# TT1-1-Top.net
KiCad netlist of a schematic drawn in Altium Designer
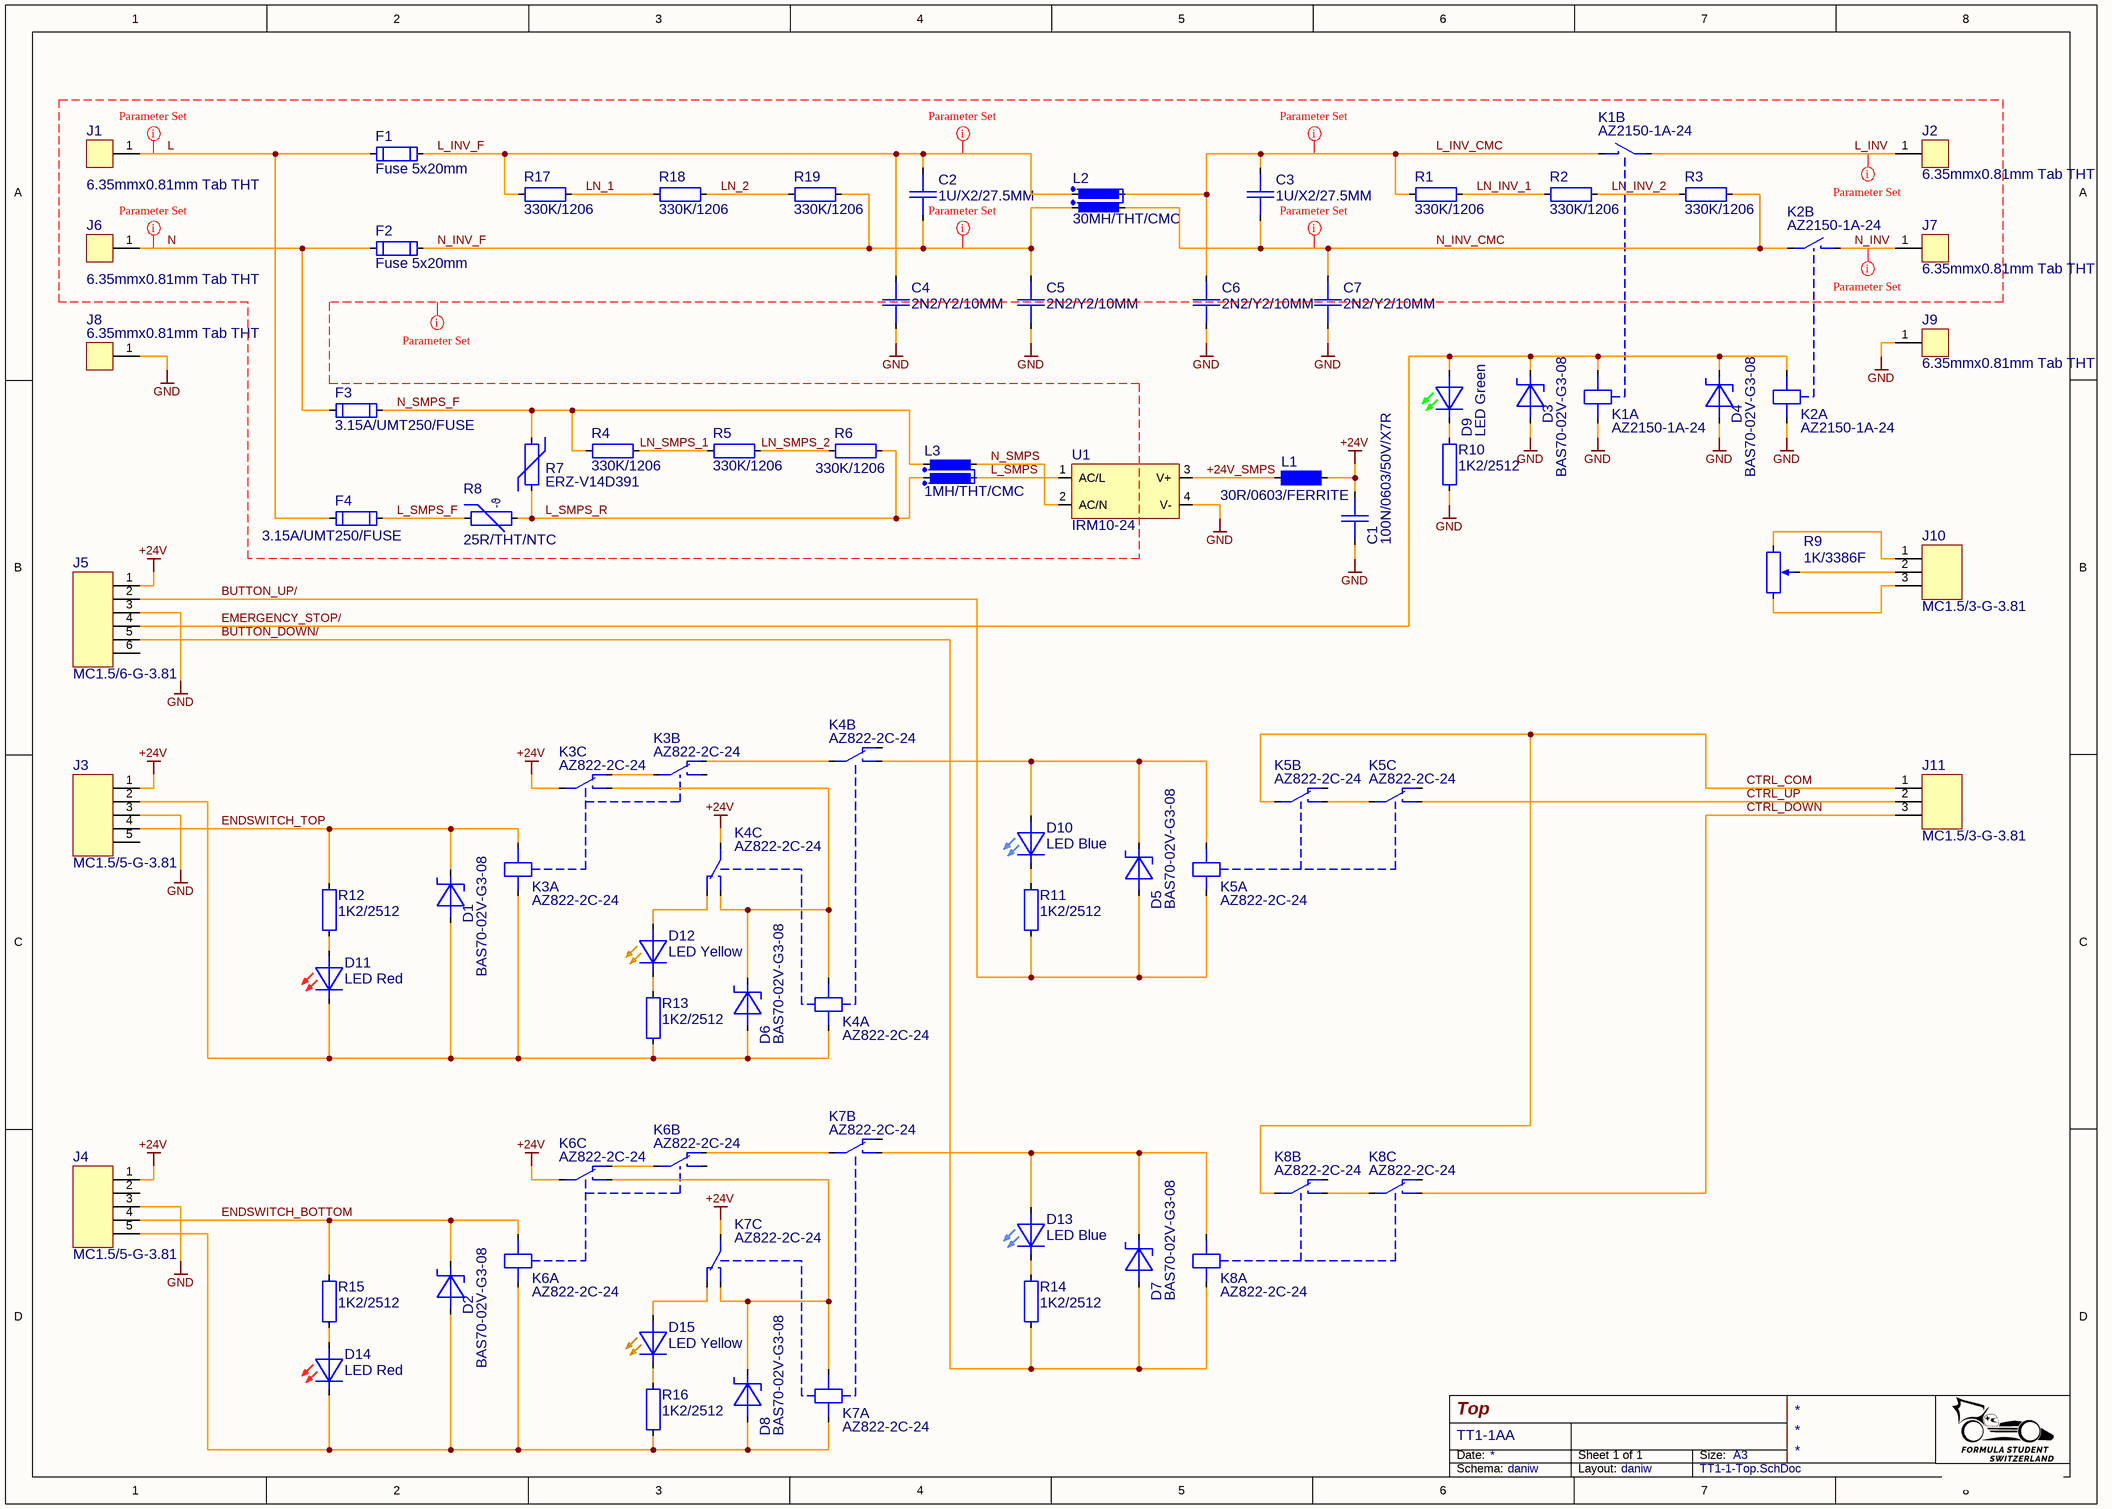
[diagram p0: TT1-1-Top.SchDoc]

(export (version "E")
  (design (tool "Eeschema 10.0.6"))
  (components
    (comp (ref "C1")
      (value "100N/0603/50V/X7R")
      (footprint "CAP0603_X7R")
      (description "CAP SM 0603 100nF 50V X7R")
      (fields (field (name "MANUFACTURER") "GENERIC"))
      (libsource (lib "daniw_altium_lib") (part "C"))
    )
    (comp (ref "C2")
      (value "1U/X2/27.5MM")
      (footprint "CAP2750P315X110X190-BL")
      (description "CAP THT 31.5X11X19 1uF 305V X2")
      (fields (field (name "MANUFACTURER") "GENERIC"))
      (libsource (lib "daniw_altium_lib") (part "C"))
    )
    (comp (ref "C3")
      (value "1U/X2/27.5MM")
      (footprint "CAP2750P315X110X190-BL")
      (description "CAP THT 31.5X11X19 1uF 305V X2")
      (fields (field (name "MANUFACTURER") "GENERIC"))
      (libsource (lib "daniw_altium_lib") (part "C"))
    )
    (comp (ref "C4")
      (value "2N2/Y2/10MM")
      (footprint "CAP1000P130X40X90-BL")
      (description "CAP THT 13X4X9 2.2nF 300V Y2")
      (fields (field (name "MANUFACTURER") "GENERIC"))
      (libsource (lib "daniw_altium_lib") (part "C"))
    )
    (comp (ref "C5")
      (value "2N2/Y2/10MM")
      (footprint "CAP1000P130X40X90-BL")
      (description "CAP THT 13X4X9 2.2nF 300V Y2")
      (fields (field (name "MANUFACTURER") "GENERIC"))
      (libsource (lib "daniw_altium_lib") (part "C"))
    )
    (comp (ref "C6")
      (value "2N2/Y2/10MM")
      (footprint "CAP1000P130X40X90-BL")
      (description "CAP THT 13X4X9 2.2nF 300V Y2")
      (fields (field (name "MANUFACTURER") "GENERIC"))
      (libsource (lib "daniw_altium_lib") (part "C"))
    )
    (comp (ref "C7")
      (value "2N2/Y2/10MM")
      (footprint "CAP1000P130X40X90-BL")
      (description "CAP THT 13X4X9 2.2nF 300V Y2")
      (fields (field (name "MANUFACTURER") "GENERIC"))
      (libsource (lib "daniw_altium_lib") (part "C"))
    )
    (comp (ref "D1")
      (value "BAS70-02V-G3-08")
      (footprint "SOD1608X065")
      (description "Small Signal Schottky Diode")
      (fields (field (name "MANUFACTURER") "Vishay"))
      (libsource (lib "daniw_altium_lib") (part "D_Schottky"))
    )
    (comp (ref "D2")
      (value "BAS70-02V-G3-08")
      (footprint "SOD1608X065")
      (description "Small Signal Schottky Diode")
      (fields (field (name "MANUFACTURER") "Vishay"))
      (libsource (lib "daniw_altium_lib") (part "D_Schottky"))
    )
    (comp (ref "D3")
      (value "BAS70-02V-G3-08")
      (footprint "SOD1608X065")
      (description "Small Signal Schottky Diode")
      (fields (field (name "MANUFACTURER") "Vishay"))
      (libsource (lib "daniw_altium_lib") (part "D_Schottky"))
    )
    (comp (ref "D4")
      (value "BAS70-02V-G3-08")
      (footprint "SOD1608X065")
      (description "Small Signal Schottky Diode")
      (fields (field (name "MANUFACTURER") "Vishay"))
      (libsource (lib "daniw_altium_lib") (part "D_Schottky"))
    )
    (comp (ref "D5")
      (value "BAS70-02V-G3-08")
      (footprint "SOD1608X065")
      (description "Small Signal Schottky Diode")
      (fields (field (name "MANUFACTURER") "Vishay"))
      (libsource (lib "daniw_altium_lib") (part "D_Schottky"))
    )
    (comp (ref "D6")
      (value "BAS70-02V-G3-08")
      (footprint "SOD1608X065")
      (description "Small Signal Schottky Diode")
      (fields (field (name "MANUFACTURER") "Vishay"))
      (libsource (lib "daniw_altium_lib") (part "D_Schottky"))
    )
    (comp (ref "D7")
      (value "BAS70-02V-G3-08")
      (footprint "SOD1608X065")
      (description "Small Signal Schottky Diode")
      (fields (field (name "MANUFACTURER") "Vishay"))
      (libsource (lib "daniw_altium_lib") (part "D_Schottky"))
    )
    (comp (ref "D8")
      (value "BAS70-02V-G3-08")
      (footprint "SOD1608X065")
      (description "Small Signal Schottky Diode")
      (fields (field (name "MANUFACTURER") "Vishay"))
      (libsource (lib "daniw_altium_lib") (part "D_Schottky"))
    )
    (comp (ref "D9")
      (value "LED Green")
      (footprint "LED0603_GREEN")
      (description "Generic LED Green 0603")
      (fields (field (name "PART NUMBER") "LED Green 0603") (field (name "MANUFACTURER") "GENERIC"))
      (libsource (lib "daniw_altium_lib") (part "LED_GREEN"))
    )
    (comp (ref "D10")
      (value "LED Blue")
      (footprint "LED0603_BLUE")
      (description "Generic LED Blue 0603")
      (fields (field (name "PART NUMBER") "LED Blue 0603") (field (name "MANUFACTURER") "GENERIC"))
      (libsource (lib "daniw_altium_lib") (part "LED_BLUE"))
    )
    (comp (ref "D11")
      (value "LED Red")
      (footprint "LED0603_RED")
      (description "Generic LED Red 0603")
      (fields (field (name "PART NUMBER") "LED Red 0603") (field (name "MANUFACTURER") "GENERIC"))
      (libsource (lib "daniw_altium_lib") (part "LED_RED"))
    )
    (comp (ref "D12")
      (value "LED Yellow")
      (footprint "LED0603_YELLOW")
      (description "Generic LED Yellow 0603")
      (fields (field (name "PART NUMBER") "LED Yellow 0603") (field (name "MANUFACTURER") "GENERIC"))
      (libsource (lib "daniw_altium_lib") (part "LED_YELLOW"))
    )
    (comp (ref "D13")
      (value "LED Blue")
      (footprint "LED0603_BLUE")
      (description "Generic LED Blue 0603")
      (fields (field (name "PART NUMBER") "LED Blue 0603") (field (name "MANUFACTURER") "GENERIC"))
      (libsource (lib "daniw_altium_lib") (part "LED_BLUE"))
    )
    (comp (ref "D14")
      (value "LED Red")
      (footprint "LED0603_RED")
      (description "Generic LED Red 0603")
      (fields (field (name "PART NUMBER") "LED Red 0603") (field (name "MANUFACTURER") "GENERIC"))
      (libsource (lib "daniw_altium_lib") (part "LED_RED"))
    )
    (comp (ref "D15")
      (value "LED Yellow")
      (footprint "LED0603_YELLOW")
      (description "Generic LED Yellow 0603")
      (fields (field (name "PART NUMBER") "LED Yellow 0603") (field (name "MANUFACTURER") "GENERIC"))
      (libsource (lib "daniw_altium_lib") (part "LED_YELLOW"))
    )
    (comp (ref "F1")
      (value "Fuse 5x20mm")
      (footprint "OGN_THR")
      (description "open fuse holder, 5 x 20 mm, THR, IEC 60335-1")
      (fields (field (name "PART NUMBER") "Fuse/5x20mm/OGN") (field (name "MANUFACTURER") "Schurter"))
      (libsource (lib "daniw_altium_lib") (part "Fuse"))
    )
    (comp (ref "F2")
      (value "Fuse 5x20mm")
      (footprint "OGN_THR")
      (description "open fuse holder, 5 x 20 mm, THR, IEC 60335-1")
      (fields (field (name "PART NUMBER") "Fuse/5x20mm/OGN") (field (name "MANUFACTURER") "Schurter"))
      (libsource (lib "daniw_altium_lib") (part "Fuse"))
    )
    (comp (ref "F3")
      (value "3.15A/UMT250/FUSE")
      (footprint "UMT250")
      (description "Fuse 250VAC 3.15A UMT250")
      (fields (field (name "MANUFACTURER") "Schurter"))
      (libsource (lib "daniw_altium_lib") (part "Fuse"))
    )
    (comp (ref "F4")
      (value "3.15A/UMT250/FUSE")
      (footprint "UMT250")
      (description "Fuse 250VAC 3.15A UMT250")
      (fields (field (name "MANUFACTURER") "Schurter"))
      (libsource (lib "daniw_altium_lib") (part "Fuse"))
    )
    (comp (ref "J1")
      (value "6.35mmx0.81mm Tab THT")
      (footprint "Tab_THT_635")
      (description "CONN QC TAB 0.250 SOLDER")
      (fields (field (name "PART NUMBER") "Tab_025_THT") (field (name "MANUFACTURER") "GENERIC"))
      (libsource (lib "daniw_altium_lib") (part "CON1"))
    )
    (comp (ref "J2")
      (value "6.35mmx0.81mm Tab THT")
      (footprint "Tab_THT_635")
      (description "CONN QC TAB 0.250 SOLDER")
      (fields (field (name "PART NUMBER") "Tab_025_THT") (field (name "MANUFACTURER") "GENERIC"))
      (libsource (lib "") (part "CON1_1"))
    )
    (comp (ref "J3")
      (value "MC1.5/5-G-3.81")
      (footprint "MC1.5/5-G-3.81")
      (description "Phoenix contact MC 1,5/ 5-G-3,81")
      (fields (field (name "MANUFACTURER") "Phoenix"))
      (libsource (lib "daniw_altium_lib") (part "CON5"))
    )
    (comp (ref "J4")
      (value "MC1.5/5-G-3.81")
      (footprint "MC1.5/5-G-3.81")
      (description "Phoenix contact MC 1,5/ 5-G-3,81")
      (fields (field (name "MANUFACTURER") "Phoenix"))
      (libsource (lib "daniw_altium_lib") (part "CON5"))
    )
    (comp (ref "J5")
      (value "MC1.5/6-G-3.81")
      (footprint "MC1.5/6-G-3.81")
      (description "Phoenix contact MC 1,5/ 6-G-3,81")
      (fields (field (name "MANUFACTURER") "Phoenix"))
      (libsource (lib "daniw_altium_lib") (part "CON6"))
    )
    (comp (ref "J6")
      (value "6.35mmx0.81mm Tab THT")
      (footprint "Tab_THT_635")
      (description "CONN QC TAB 0.250 SOLDER")
      (fields (field (name "PART NUMBER") "Tab_025_THT") (field (name "MANUFACTURER") "GENERIC"))
      (libsource (lib "daniw_altium_lib") (part "CON1"))
    )
    (comp (ref "J7")
      (value "6.35mmx0.81mm Tab THT")
      (footprint "Tab_THT_635")
      (description "CONN QC TAB 0.250 SOLDER")
      (fields (field (name "PART NUMBER") "Tab_025_THT") (field (name "MANUFACTURER") "GENERIC"))
      (libsource (lib "") (part "CON1_1"))
    )
    (comp (ref "J8")
      (value "6.35mmx0.81mm Tab THT")
      (footprint "Tab_THT_635")
      (description "CONN QC TAB 0.250 SOLDER")
      (fields (field (name "PART NUMBER") "Tab_025_THT") (field (name "MANUFACTURER") "GENERIC"))
      (libsource (lib "daniw_altium_lib") (part "CON1"))
    )
    (comp (ref "J9")
      (value "6.35mmx0.81mm Tab THT")
      (footprint "Tab_THT_635")
      (description "CONN QC TAB 0.250 SOLDER")
      (fields (field (name "PART NUMBER") "Tab_025_THT") (field (name "MANUFACTURER") "GENERIC"))
      (libsource (lib "") (part "CON1_1"))
    )
    (comp (ref "J10")
      (value "MC1.5/3-G-3.81")
      (footprint "MC1.5/3-G-3.81")
      (description "Phoenix contact MC 1,5/ 3-G-3,81")
      (fields (field (name "MANUFACTURER") "Phoenix"))
      (libsource (lib "daniw_altium_lib") (part "CON3"))
    )
    (comp (ref "J11")
      (value "MC1.5/3-G-3.81")
      (footprint "MC1.5/3-G-3.81")
      (description "Phoenix contact MC 1,5/ 3-G-3,81")
      (fields (field (name "MANUFACTURER") "Phoenix"))
      (libsource (lib "daniw_altium_lib") (part "CON3"))
    )
    (comp (ref "K1")
      (value "AZ2150-1A-24")
      (footprint "AZ2150-SPST-NO")
      (description "Miniature Power Relay, SPST-NO, 24V Coil, 40A 30VDC 300VAC")
      (fields (field (name "MANUFACTURER") "Zettler"))
      (libsource (lib "daniw_altium_lib") (part "REL_SPST_NO"))
    )
    (comp (ref "K2")
      (value "AZ2150-1A-24")
      (footprint "AZ2150-SPST-NO")
      (description "Miniature Power Relay, SPST-NO, 24V Coil, 40A 30VDC 300VAC")
      (fields (field (name "MANUFACTURER") "Zettler"))
      (libsource (lib "daniw_altium_lib") (part "REL_SPST_NO"))
    )
    (comp (ref "K3")
      (value "AZ822-2C-24")
      (footprint "AZ822")
      (description "Subminiature DIP Relay, DPDT, 24V 98mW Coil, 2A 220VDC 250VAC")
      (fields (field (name "MANUFACTURER") "Zettler"))
      (libsource (lib "daniw_altium_lib") (part "REL_DPDT"))
    )
    (comp (ref "K4")
      (value "AZ822-2C-24")
      (footprint "AZ822")
      (description "Subminiature DIP Relay, DPDT, 24V 98mW Coil, 2A 220VDC 250VAC")
      (fields (field (name "MANUFACTURER") "Zettler"))
      (libsource (lib "daniw_altium_lib") (part "REL_DPDT"))
    )
    (comp (ref "K5")
      (value "AZ822-2C-24")
      (footprint "AZ822")
      (description "Subminiature DIP Relay, DPDT, 24V 98mW Coil, 2A 220VDC 250VAC")
      (fields (field (name "MANUFACTURER") "Zettler"))
      (libsource (lib "daniw_altium_lib") (part "REL_DPDT"))
    )
    (comp (ref "K6")
      (value "AZ822-2C-24")
      (footprint "AZ822")
      (description "Subminiature DIP Relay, DPDT, 24V 98mW Coil, 2A 220VDC 250VAC")
      (fields (field (name "MANUFACTURER") "Zettler"))
      (libsource (lib "daniw_altium_lib") (part "REL_DPDT"))
    )
    (comp (ref "K7")
      (value "AZ822-2C-24")
      (footprint "AZ822")
      (description "Subminiature DIP Relay, DPDT, 24V 98mW Coil, 2A 220VDC 250VAC")
      (fields (field (name "MANUFACTURER") "Zettler"))
      (libsource (lib "daniw_altium_lib") (part "REL_DPDT"))
    )
    (comp (ref "K8")
      (value "AZ822-2C-24")
      (footprint "AZ822")
      (description "Subminiature DIP Relay, DPDT, 24V 98mW Coil, 2A 220VDC 250VAC")
      (fields (field (name "MANUFACTURER") "Zettler"))
      (libsource (lib "daniw_altium_lib") (part "REL_DPDT"))
    )
    (comp (ref "L1")
      (value "30R/0603/FERRITE")
      (footprint "FB0603")
      (description "30R@100MHz 5A 0603 Ferrite")
      (fields (field (name "MANUFACTURER") "GENERIC"))
      (libsource (lib "daniw_altium_lib") (part "Ferrite"))
    )
    (comp (ref "L2")
      (value "30MH/THT/CMC")
      (footprint "CMC-WE-CMBNC-XL-7448050530")
      (description "CMC 30mH 5A Würth CMBNC 7448050530")
      (fields (field (name "MANUFACTURER") "Würth"))
      (libsource (lib "daniw_altium_lib") (part "L_CMC_2"))
    )
    (comp (ref "L3")
      (value "1MH/THT/CMC")
      (footprint "DFKH-CASE-50-2")
      (description "CMC 1mH 2A THT Schurter DFKH-14-0003")
      (fields (field (name "MANUFACTURER") "SCHURTER"))
      (libsource (lib "") (part "L_CMC_2_1"))
    )
    (comp (ref "R1")
      (value "330K/1206")
      (footprint "R1206-0.80-WW")
      (description "RES SM 1206 330K")
      (fields (field (name "MANUFACTURER") "GENERIC"))
      (libsource (lib "daniw_altium_lib") (part "R"))
    )
    (comp (ref "R2")
      (value "330K/1206")
      (footprint "R1206-0.80-WW")
      (description "RES SM 1206 330K")
      (fields (field (name "MANUFACTURER") "GENERIC"))
      (libsource (lib "daniw_altium_lib") (part "R"))
    )
    (comp (ref "R3")
      (value "330K/1206")
      (footprint "R1206-0.80-WW")
      (description "RES SM 1206 330K")
      (fields (field (name "MANUFACTURER") "GENERIC"))
      (libsource (lib "daniw_altium_lib") (part "R"))
    )
    (comp (ref "R4")
      (value "330K/1206")
      (footprint "R1206-0.80-WW")
      (description "RES SM 1206 330K")
      (fields (field (name "MANUFACTURER") "GENERIC"))
      (libsource (lib "daniw_altium_lib") (part "R"))
    )
    (comp (ref "R5")
      (value "330K/1206")
      (footprint "R1206-0.80-WW")
      (description "RES SM 1206 330K")
      (fields (field (name "MANUFACTURER") "GENERIC"))
      (libsource (lib "daniw_altium_lib") (part "R"))
    )
    (comp (ref "R6")
      (value "330K/1206")
      (footprint "R1206-0.80-WW")
      (description "RES SM 1206 330K")
      (fields (field (name "MANUFACTURER") "GENERIC"))
      (libsource (lib "daniw_altium_lib") (part "R"))
    )
    (comp (ref "R7")
      (value "ERZ-V14D391")
      (footprint "RESD750W80D155")
      (description "VARISTOR 391V 6kA")
      (fields (field (name "MANUFACTURER") "GENERIC"))
      (libsource (lib "daniw_altium_lib") (part "R_VAR"))
    )
    (comp (ref "R8")
      (value "25R/THT/NTC")
      (footprint "RESD500W60D115")
      (description "RES NTC THT 5 25R")
      (fields (field (name "MANUFACTURER") "GENERIC"))
      (libsource (lib "daniw_altium_lib") (part "R_NTC"))
    )
    (comp (ref "R9")
      (value "1K/3386F")
      (footprint "3386F")
      (description "RES POT 3386F 1K")
      (fields (field (name "MANUFACTURER") "Bourns"))
      (libsource (lib "daniw_altium_lib") (part "R_POT"))
    )
    (comp (ref "R10")
      (value "1K2/2512")
      (footprint "R2512-0.65-WW")
      (description "RES SM 2512 1K2")
      (fields (field (name "MANUFACTURER") "GENERIC"))
      (libsource (lib "daniw_altium_lib") (part "R"))
    )
    (comp (ref "R11")
      (value "1K2/2512")
      (footprint "R2512-0.65-WW")
      (description "RES SM 2512 1K2")
      (fields (field (name "MANUFACTURER") "GENERIC"))
      (libsource (lib "daniw_altium_lib") (part "R"))
    )
    (comp (ref "R12")
      (value "1K2/2512")
      (footprint "R2512-0.65-WW")
      (description "RES SM 2512 1K2")
      (fields (field (name "MANUFACTURER") "GENERIC"))
      (libsource (lib "daniw_altium_lib") (part "R"))
    )
    (comp (ref "R13")
      (value "1K2/2512")
      (footprint "R2512-0.65-WW")
      (description "RES SM 2512 1K2")
      (fields (field (name "MANUFACTURER") "GENERIC"))
      (libsource (lib "daniw_altium_lib") (part "R"))
    )
    (comp (ref "R14")
      (value "1K2/2512")
      (footprint "R2512-0.65-WW")
      (description "RES SM 2512 1K2")
      (fields (field (name "MANUFACTURER") "GENERIC"))
      (libsource (lib "daniw_altium_lib") (part "R"))
    )
    (comp (ref "R15")
      (value "1K2/2512")
      (footprint "R2512-0.65-WW")
      (description "RES SM 2512 1K2")
      (fields (field (name "MANUFACTURER") "GENERIC"))
      (libsource (lib "daniw_altium_lib") (part "R"))
    )
    (comp (ref "R16")
      (value "1K2/2512")
      (footprint "R2512-0.65-WW")
      (description "RES SM 2512 1K2")
      (fields (field (name "MANUFACTURER") "GENERIC"))
      (libsource (lib "daniw_altium_lib") (part "R"))
    )
    (comp (ref "R17")
      (value "330K/1206")
      (footprint "R1206-0.80-WW")
      (description "RES SM 1206 330K")
      (fields (field (name "MANUFACTURER") "GENERIC"))
      (libsource (lib "daniw_altium_lib") (part "R"))
    )
    (comp (ref "R18")
      (value "330K/1206")
      (footprint "R1206-0.80-WW")
      (description "RES SM 1206 330K")
      (fields (field (name "MANUFACTURER") "GENERIC"))
      (libsource (lib "daniw_altium_lib") (part "R"))
    )
    (comp (ref "R19")
      (value "330K/1206")
      (footprint "R1206-0.80-WW")
      (description "RES SM 1206 330K")
      (fields (field (name "MANUFACTURER") "GENERIC"))
      (libsource (lib "daniw_altium_lib") (part "R"))
    )
    (comp (ref "U1")
      (value "IRM10-24")
      (footprint "IRM10")
      (description "10W AC-DC PCB-Mount Green Power Module, 24V")
      (libsource (lib "daniw_altium_lib") (part "IRM30"))
    )
  )
  (nets
    (net (code "1") (name "+24V") (class "Default")
      (node (ref "C1") (pin "1") (pinfunction "1_1") (pintype "passive"))
      (node (ref "J3") (pin "1") (pintype "passive"))
      (node (ref "J4") (pin "1") (pintype "passive"))
      (node (ref "J5") (pin "1") (pintype "passive"))
      (node (ref "K3") (pin "6") (pinfunction "COM2_6") (pintype "passive"))
      (node (ref "K4") (pin "6") (pinfunction "COM2_6") (pintype "passive"))
      (node (ref "K6") (pin "6") (pinfunction "COM2_6") (pintype "passive"))
      (node (ref "K7") (pin "6") (pinfunction "COM2_6") (pintype "passive"))
      (node (ref "L1") (pin "2") (pinfunction "2_2") (pintype "passive"))
    )
    (net (code "2") (name "/+24V_SMPS") (class "Default")
      (node (ref "L1") (pin "1") (pinfunction "1_1") (pintype "passive"))
      (node (ref "U1") (pin "3") (pinfunction "V+_3") (pintype "passive"))
    )
    (net (code "3") (name "/BUTTON_DOWN{slash}") (class "Default")
      (node (ref "D7") (pin "2") (pinfunction "2_2") (pintype "passive"))
      (node (ref "J5") (pin "5") (pintype "passive"))
      (node (ref "K8") (pin "2") (pinfunction "2_2") (pintype "passive"))
      (node (ref "R14") (pin "2") (pinfunction "2_2") (pintype "passive"))
    )
    (net (code "4") (name "/BUTTON_UP{slash}") (class "Default")
      (node (ref "D5") (pin "2") (pinfunction "2_2") (pintype "passive"))
      (node (ref "J5") (pin "2") (pintype "passive"))
      (node (ref "K5") (pin "1") (pinfunction "1_1") (pintype "passive"))
      (node (ref "R11") (pin "2") (pinfunction "2_2") (pintype "passive"))
    )
    (net (code "5") (name "/CTRL_COM") (class "Default")
      (node (ref "J11") (pin "1") (pintype "passive"))
      (node (ref "K5") (pin "3") (pinfunction "COM1_3") (pintype "passive"))
      (node (ref "K8") (pin "3") (pinfunction "COM1_3") (pintype "passive"))
    )
    (net (code "6") (name "/CTRL_DOWN") (class "Default")
      (node (ref "J11") (pin "3") (pintype "passive"))
      (node (ref "K8") (pin "8") (pinfunction "NO2_8") (pintype "passive"))
    )
    (net (code "7") (name "/CTRL_UP") (class "Default")
      (node (ref "J11") (pin "2") (pintype "passive"))
      (node (ref "K5") (pin "8") (pinfunction "NO2_8") (pintype "passive"))
    )
    (net (code "8") (name "/EMERGENCY_STOP{slash}") (class "Default")
      (node (ref "D3") (pin "1") (pinfunction "1_1") (pintype "passive"))
      (node (ref "D4") (pin "1") (pinfunction "1_1") (pintype "passive"))
      (node (ref "D9") (pin "2") (pinfunction "2_2") (pintype "passive"))
      (node (ref "J5") (pin "4") (pintype "passive"))
      (node (ref "K1") (pin "1") (pinfunction "1_1") (pintype "passive"))
      (node (ref "K2") (pin "1") (pinfunction "1_1") (pintype "passive"))
    )
    (net (code "9") (name "/ENDSWITCH_BOTTOM") (class "Default")
      (node (ref "D2") (pin "1") (pinfunction "1_1") (pintype "passive"))
      (node (ref "J4") (pin "4") (pintype "passive"))
      (node (ref "K6") (pin "1") (pinfunction "1_1") (pintype "passive"))
      (node (ref "R15") (pin "1") (pinfunction "1_1") (pintype "passive"))
    )
    (net (code "10") (name "/ENDSWITCH_TOP") (class "Default")
      (node (ref "D1") (pin "1") (pinfunction "1_1") (pintype "passive"))
      (node (ref "J3") (pin "4") (pintype "passive"))
      (node (ref "K3") (pin "1") (pinfunction "1_1") (pintype "passive"))
      (node (ref "R12") (pin "1") (pinfunction "1_1") (pintype "passive"))
    )
    (net (code "11") (name "/L") (class "Default")
      (node (ref "F1") (pin "1") (pinfunction "1_1") (pintype "passive"))
      (node (ref "F4") (pin "1") (pinfunction "1_1") (pintype "passive"))
      (node (ref "J1") (pin "1") (pintype "passive"))
    )
    (net (code "12") (name "/LN_1") (class "Default")
      (node (ref "R17") (pin "2") (pinfunction "2_2") (pintype "passive"))
      (node (ref "R18") (pin "1") (pinfunction "1_1") (pintype "passive"))
    )
    (net (code "13") (name "/LN_2") (class "Default")
      (node (ref "R18") (pin "2") (pinfunction "2_2") (pintype "passive"))
      (node (ref "R19") (pin "1") (pinfunction "1_1") (pintype "passive"))
    )
    (net (code "14") (name "/LN_INV_1") (class "Default")
      (node (ref "R1") (pin "2") (pinfunction "2_2") (pintype "passive"))
      (node (ref "R2") (pin "1") (pinfunction "1_1") (pintype "passive"))
    )
    (net (code "15") (name "/LN_INV_2") (class "Default")
      (node (ref "R2") (pin "2") (pinfunction "2_2") (pintype "passive"))
      (node (ref "R3") (pin "1") (pinfunction "1_1") (pintype "passive"))
    )
    (net (code "16") (name "/LN_SMPS_1") (class "Default")
      (node (ref "R4") (pin "2") (pinfunction "2_2") (pintype "passive"))
      (node (ref "R5") (pin "2") (pinfunction "2_2") (pintype "passive"))
    )
    (net (code "17") (name "/LN_SMPS_2") (class "Default")
      (node (ref "R5") (pin "1") (pinfunction "1_1") (pintype "passive"))
      (node (ref "R6") (pin "1") (pinfunction "1_1") (pintype "passive"))
    )
    (net (code "18") (name "/L_INV") (class "Default")
      (node (ref "J2") (pin "1") (pintype "passive"))
      (node (ref "K1") (pin "3") (pinfunction "COM1_3") (pintype "passive"))
    )
    (net (code "19") (name "/L_INV_CMC") (class "Default")
      (node (ref "C3") (pin "1") (pinfunction "1_1") (pintype "passive"))
      (node (ref "C6") (pin "1") (pinfunction "1_1") (pintype "passive"))
      (node (ref "K1") (pin "4") (pinfunction "NO1_4") (pintype "passive"))
      (node (ref "L2") (pin "4") (pinfunction "4_4") (pintype "passive"))
      (node (ref "R1") (pin "1") (pinfunction "1_1") (pintype "passive"))
    )
    (net (code "20") (name "/L_INV_F") (class "Default")
      (node (ref "C2") (pin "1") (pinfunction "1_1") (pintype "passive"))
      (node (ref "C4") (pin "1") (pinfunction "1_1") (pintype "passive"))
      (node (ref "F1") (pin "2") (pinfunction "2_2") (pintype "passive"))
      (node (ref "L2") (pin "2") (pinfunction "2_2") (pintype "passive"))
      (node (ref "R17") (pin "1") (pinfunction "1_1") (pintype "passive"))
    )
    (net (code "21") (name "/L_SMPS") (class "Default")
      (node (ref "L3") (pin "4") (pinfunction "4_4") (pintype "passive"))
      (node (ref "U1") (pin "1") (pinfunction "AC/L_1") (pintype "passive"))
    )
    (net (code "22") (name "/L_SMPS_F") (class "Default")
      (node (ref "F4") (pin "2") (pinfunction "2_2") (pintype "passive"))
      (node (ref "R8") (pin "1") (pinfunction "1_1") (pintype "passive"))
    )
    (net (code "23") (name "/L_SMPS_R") (class "Default")
      (node (ref "L3") (pin "2") (pinfunction "2_2") (pintype "passive"))
      (node (ref "R6") (pin "2") (pinfunction "2_2") (pintype "passive"))
      (node (ref "R7") (pin "2") (pinfunction "2_2") (pintype "passive"))
      (node (ref "R8") (pin "2") (pinfunction "2_2") (pintype "passive"))
    )
    (net (code "24") (name "/N") (class "Default")
      (node (ref "F2") (pin "1") (pinfunction "1_1") (pintype "passive"))
      (node (ref "F3") (pin "1") (pinfunction "1_1") (pintype "passive"))
      (node (ref "J6") (pin "1") (pintype "passive"))
    )
    (net (code "25") (name "/N_INV") (class "Default")
      (node (ref "J7") (pin "1") (pintype "passive"))
      (node (ref "K2") (pin "4") (pinfunction "NO1_4") (pintype "passive"))
    )
    (net (code "26") (name "/N_INV_CMC") (class "Default")
      (node (ref "C3") (pin "2") (pinfunction "2_2") (pintype "passive"))
      (node (ref "C7") (pin "1") (pinfunction "1_1") (pintype "passive"))
      (node (ref "K2") (pin "3") (pinfunction "COM1_3") (pintype "passive"))
      (node (ref "L2") (pin "3") (pinfunction "3_3") (pintype "passive"))
      (node (ref "R3") (pin "2") (pinfunction "2_2") (pintype "passive"))
    )
    (net (code "27") (name "/N_INV_F") (class "Default")
      (node (ref "C2") (pin "2") (pinfunction "2_2") (pintype "passive"))
      (node (ref "C5") (pin "1") (pinfunction "1_1") (pintype "passive"))
      (node (ref "F2") (pin "2") (pinfunction "2_2") (pintype "passive"))
      (node (ref "L2") (pin "1") (pinfunction "1_1") (pintype "passive"))
      (node (ref "R19") (pin "2") (pinfunction "2_2") (pintype "passive"))
    )
    (net (code "28") (name "/N_SMPS") (class "Default")
      (node (ref "L3") (pin "3") (pinfunction "3_3") (pintype "passive"))
      (node (ref "U1") (pin "2") (pinfunction "AC/N_2") (pintype "passive"))
    )
    (net (code "29") (name "/N_SMPS_F") (class "Default")
      (node (ref "F3") (pin "2") (pinfunction "2_2") (pintype "passive"))
      (node (ref "L3") (pin "1") (pinfunction "1_1") (pintype "passive"))
      (node (ref "R4") (pin "1") (pinfunction "1_1") (pintype "passive"))
      (node (ref "R7") (pin "1") (pinfunction "1_1") (pintype "passive"))
    )
    (net (code "30") (name "GND") (class "Default")
      (node (ref "C1") (pin "2") (pinfunction "2_2") (pintype "passive"))
      (node (ref "C4") (pin "2") (pinfunction "2_2") (pintype "passive"))
      (node (ref "C5") (pin "2") (pinfunction "2_2") (pintype "passive"))
      (node (ref "C6") (pin "2") (pinfunction "2_2") (pintype "passive"))
      (node (ref "C7") (pin "2") (pinfunction "2_2") (pintype "passive"))
      (node (ref "D3") (pin "2") (pinfunction "2_2") (pintype "passive"))
      (node (ref "D4") (pin "2") (pinfunction "2_2") (pintype "passive"))
      (node (ref "J3") (pin "3") (pintype "passive"))
      (node (ref "J4") (pin "3") (pintype "passive"))
      (node (ref "J5") (pin "3") (pintype "passive"))
      (node (ref "J8") (pin "1") (pintype "passive"))
      (node (ref "J9") (pin "1") (pintype "passive"))
      (node (ref "K1") (pin "2") (pinfunction "2_2") (pintype "passive"))
      (node (ref "K2") (pin "2") (pinfunction "2_2") (pintype "passive"))
      (node (ref "R10") (pin "2") (pinfunction "2_2") (pintype "passive"))
      (node (ref "U1") (pin "4") (pinfunction "V-_4") (pintype "passive"))
    )
    (net (code "31") (name "Net-(D1-Pad2)") (class "Default")
      (node (ref "D1") (pin "2") (pinfunction "2_2") (pintype "passive"))
      (node (ref "D11") (pin "1") (pinfunction "1_1") (pintype "passive"))
      (node (ref "D6") (pin "2") (pinfunction "2_2") (pintype "passive"))
      (node (ref "J3") (pin "2") (pintype "passive"))
      (node (ref "K3") (pin "2") (pinfunction "2_2") (pintype "passive"))
      (node (ref "K4") (pin "2") (pinfunction "2_2") (pintype "passive"))
      (node (ref "R13") (pin "2") (pinfunction "2_2") (pintype "passive"))
    )
    (net (code "32") (name "Net-(D9-Pad1)") (class "Default")
      (node (ref "D9") (pin "1") (pinfunction "1_1") (pintype "passive"))
      (node (ref "R10") (pin "1") (pinfunction "1_1") (pintype "passive"))
    )
    (net (code "33") (name "Net-(D10-Pad1)") (class "Default")
      (node (ref "D10") (pin "1") (pinfunction "1_1") (pintype "passive"))
      (node (ref "R11") (pin "1") (pinfunction "1_1") (pintype "passive"))
    )
    (net (code "34") (name "Net-(D11-Pad2)") (class "Default")
      (node (ref "D11") (pin "2") (pinfunction "2_2") (pintype "passive"))
      (node (ref "R12") (pin "2") (pinfunction "2_2") (pintype "passive"))
    )
    (net (code "35") (name "Net-(D12-Pad1)") (class "Default")
      (node (ref "D12") (pin "1") (pinfunction "1_1") (pintype "passive"))
      (node (ref "R13") (pin "1") (pinfunction "1_1") (pintype "passive"))
    )
    (net (code "36") (name "Net-(D13-Pad1)") (class "Default")
      (node (ref "D13") (pin "1") (pinfunction "1_1") (pintype "passive"))
      (node (ref "R14") (pin "1") (pinfunction "1_1") (pintype "passive"))
    )
    (net (code "37") (name "Net-(D14-Pad1)") (class "Default")
      (node (ref "D14") (pin "1") (pinfunction "1_1") (pintype "passive"))
      (node (ref "D2") (pin "2") (pinfunction "2_2") (pintype "passive"))
      (node (ref "D8") (pin "2") (pinfunction "2_2") (pintype "passive"))
      (node (ref "J4") (pin "5") (pintype "passive"))
      (node (ref "K6") (pin "2") (pinfunction "2_2") (pintype "passive"))
      (node (ref "K7") (pin "2") (pinfunction "2_2") (pintype "passive"))
      (node (ref "R16") (pin "2") (pinfunction "2_2") (pintype "passive"))
    )
    (net (code "38") (name "Net-(D14-Pad2)") (class "Default")
      (node (ref "D14") (pin "2") (pinfunction "2_2") (pintype "passive"))
      (node (ref "R15") (pin "2") (pinfunction "2_2") (pintype "passive"))
    )
    (net (code "39") (name "Net-(D15-Pad1)") (class "Default")
      (node (ref "D15") (pin "1") (pinfunction "1_1") (pintype "passive"))
      (node (ref "R16") (pin "1") (pinfunction "1_1") (pintype "passive"))
    )
    (net (code "40") (name "Net-(J10-Pad1)") (class "Default")
      (node (ref "J10") (pin "1") (pintype "passive"))
      (node (ref "R9") (pin "1") (pinfunction "1_1") (pintype "passive"))
    )
    (net (code "41") (name "Net-(J10-Pad2)") (class "Default")
      (node (ref "J10") (pin "2") (pintype "passive"))
      (node (ref "R9") (pin "3") (pinfunction "3_3") (pintype "passive"))
    )
    (net (code "42") (name "Net-(J10-Pad3)") (class "Default")
      (node (ref "J10") (pin "3") (pintype "passive"))
      (node (ref "R9") (pin "2") (pinfunction "2_2") (pintype "passive"))
    )
    (net (code "43") (name "Net-(K3B-COM1)") (class "Default")
      (node (ref "K3") (pin "3") (pinfunction "COM1_3") (pintype "passive"))
      (node (ref "K3") (pin "7") (pinfunction "NC2_7") (pintype "passive"))
    )
    (net (code "44") (name "Net-(K3B-NC1)") (class "Default")
      (node (ref "K3") (pin "4") (pinfunction "NC1_4") (pintype "passive"))
      (node (ref "K4") (pin "3") (pinfunction "COM1_3") (pintype "passive"))
    )
    (net (code "45") (name "Net-(K3C-NO2)") (class "Default")
      (node (ref "D6") (pin "1") (pinfunction "1_1") (pintype "passive"))
      (node (ref "K3") (pin "8") (pinfunction "NO2_8") (pintype "passive"))
      (node (ref "K4") (pin "1") (pinfunction "1_1") (pintype "passive"))
      (node (ref "K4") (pin "8") (pinfunction "NO2_8") (pintype "passive"))
    )
    (net (code "46") (name "Net-(K4B-NO1)") (class "Default")
      (node (ref "D10") (pin "2") (pinfunction "2_2") (pintype "passive"))
      (node (ref "D5") (pin "1") (pinfunction "1_1") (pintype "passive"))
      (node (ref "K4") (pin "5") (pinfunction "NO1_5") (pintype "passive"))
      (node (ref "K5") (pin "2") (pinfunction "2_2") (pintype "passive"))
    )
    (net (code "47") (name "Net-(K4C-NC2)") (class "Default")
      (node (ref "D12") (pin "2") (pinfunction "2_2") (pintype "passive"))
      (node (ref "K4") (pin "7") (pinfunction "NC2_7") (pintype "passive"))
    )
    (net (code "48") (name "Net-(K5B-NO1)") (class "Default")
      (node (ref "K5") (pin "5") (pinfunction "NO1_5") (pintype "passive"))
      (node (ref "K5") (pin "6") (pinfunction "COM2_6") (pintype "passive"))
    )
    (net (code "49") (name "Net-(K6B-COM1)") (class "Default")
      (node (ref "K6") (pin "3") (pinfunction "COM1_3") (pintype "passive"))
      (node (ref "K6") (pin "7") (pinfunction "NC2_7") (pintype "passive"))
    )
    (net (code "50") (name "Net-(K6B-NC1)") (class "Default")
      (node (ref "K6") (pin "4") (pinfunction "NC1_4") (pintype "passive"))
      (node (ref "K7") (pin "3") (pinfunction "COM1_3") (pintype "passive"))
    )
    (net (code "51") (name "Net-(K6C-NO2)") (class "Default")
      (node (ref "D8") (pin "1") (pinfunction "1_1") (pintype "passive"))
      (node (ref "K6") (pin "8") (pinfunction "NO2_8") (pintype "passive"))
      (node (ref "K7") (pin "1") (pinfunction "1_1") (pintype "passive"))
      (node (ref "K7") (pin "8") (pinfunction "NO2_8") (pintype "passive"))
    )
    (net (code "52") (name "Net-(K7B-NO1)") (class "Default")
      (node (ref "D13") (pin "2") (pinfunction "2_2") (pintype "passive"))
      (node (ref "D7") (pin "1") (pinfunction "1_1") (pintype "passive"))
      (node (ref "K7") (pin "5") (pinfunction "NO1_5") (pintype "passive"))
      (node (ref "K8") (pin "1") (pinfunction "1_1") (pintype "passive"))
    )
    (net (code "53") (name "Net-(K7C-NC2)") (class "Default")
      (node (ref "D15") (pin "2") (pinfunction "2_2") (pintype "passive"))
      (node (ref "K7") (pin "7") (pinfunction "NC2_7") (pintype "passive"))
    )
    (net (code "54") (name "Net-(K8B-NO1)") (class "Default")
      (node (ref "K8") (pin "5") (pinfunction "NO1_5") (pintype "passive"))
      (node (ref "K8") (pin "6") (pinfunction "COM2_6") (pintype "passive"))
    )
    (net (code "55") (name "unconnected-(J3-Pad5)") (class "Default")
      (node (ref "J3") (pin "5") (pintype "passive"))
    )
    (net (code "56") (name "unconnected-(J4-Pad2)") (class "Default")
      (node (ref "J4") (pin "2") (pintype "passive"))
    )
    (net (code "57") (name "unconnected-(J5-Pad6)") (class "Default")
      (node (ref "J5") (pin "6") (pintype "passive"))
    )
    (net (code "58") (name "unconnected-(K3B-NO1-Pad5)") (class "Default")
      (node (ref "K3") (pin "5") (pinfunction "NO1_5") (pintype "passive"))
    )
    (net (code "59") (name "unconnected-(K4B-NC1-Pad4)") (class "Default")
      (node (ref "K4") (pin "4") (pinfunction "NC1_4") (pintype "passive"))
    )
    (net (code "60") (name "unconnected-(K5B-NC1-Pad4)") (class "Default")
      (node (ref "K5") (pin "4") (pinfunction "NC1_4") (pintype "passive"))
    )
    (net (code "61") (name "unconnected-(K5C-NC2-Pad7)") (class "Default")
      (node (ref "K5") (pin "7") (pinfunction "NC2_7") (pintype "passive"))
    )
    (net (code "62") (name "unconnected-(K6B-NO1-Pad5)") (class "Default")
      (node (ref "K6") (pin "5") (pinfunction "NO1_5") (pintype "passive"))
    )
    (net (code "63") (name "unconnected-(K7B-NC1-Pad4)") (class "Default")
      (node (ref "K7") (pin "4") (pinfunction "NC1_4") (pintype "passive"))
    )
    (net (code "64") (name "unconnected-(K8B-NC1-Pad4)") (class "Default")
      (node (ref "K8") (pin "4") (pinfunction "NC1_4") (pintype "passive"))
    )
    (net (code "65") (name "unconnected-(K8C-NC2-Pad7)") (class "Default")
      (node (ref "K8") (pin "7") (pinfunction "NC2_7") (pintype "passive"))
    )
  )
)
